# Leds_and_Buttons.net
KiCad netlist of a schematic drawn in Altium Designer
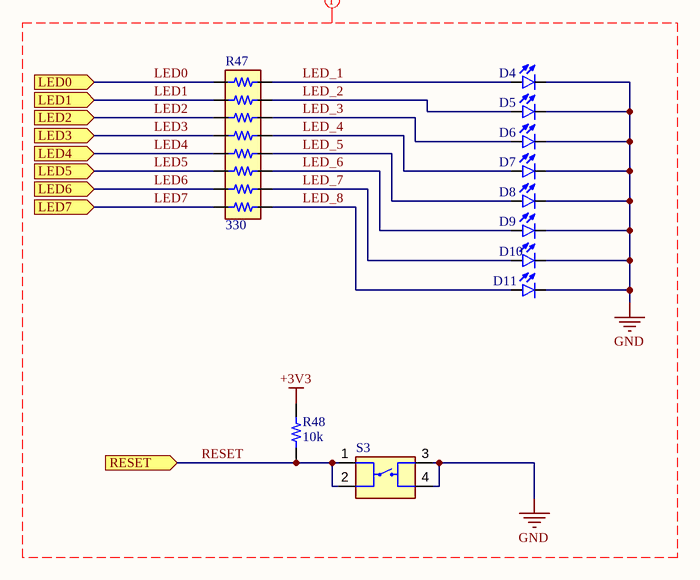
[diagram p0: Leds_and_Buttons.SchDoc]

(export (version "E")
  (design (tool "Eeschema 10.0.6"))
  (components
    (comp (ref "D4")
      (value "597-3305-607F")
      (footprint "0603_LED")
      (description "LED blue diffused 0603 SMD")
      (libsource (lib "Integrated_Circuits") (part "LED_BLUE_0603"))
    )
    (comp (ref "D5")
      (value "597-3305-607F")
      (footprint "0603_LED")
      (description "LED blue diffused 0603 SMD")
      (libsource (lib "Integrated_Circuits") (part "LED_BLUE_0603"))
    )
    (comp (ref "D6")
      (value "597-3305-607F")
      (footprint "0603_LED")
      (description "LED blue diffused 0603 SMD")
      (libsource (lib "Integrated_Circuits") (part "LED_BLUE_0603"))
    )
    (comp (ref "D7")
      (value "597-3305-607F")
      (footprint "0603_LED")
      (description "LED blue diffused 0603 SMD")
      (libsource (lib "Integrated_Circuits") (part "LED_BLUE_0603"))
    )
    (comp (ref "D8")
      (value "597-3305-607F")
      (footprint "0603_LED")
      (description "LED blue diffused 0603 SMD")
      (libsource (lib "Integrated_Circuits") (part "LED_BLUE_0603"))
    )
    (comp (ref "D9")
      (value "597-3305-607F")
      (footprint "0603_LED")
      (description "LED blue diffused 0603 SMD")
      (libsource (lib "Integrated_Circuits") (part "LED_BLUE_0603"))
    )
    (comp (ref "D10")
      (value "597-3305-607F")
      (footprint "0603_LED")
      (description "LED blue diffused 0603 SMD")
      (libsource (lib "Integrated_Circuits") (part "LED_BLUE_0603"))
    )
    (comp (ref "D11")
      (value "597-3305-607F")
      (footprint "0603_LED")
      (description "LED blue diffused 0603 SMD")
      (libsource (lib "Integrated_Circuits") (part "LED_BLUE_0603"))
    )
    (comp (ref "R47")
      (value "330")
      (footprint "ArrayResistor-1506")
      (description "RES ARRAY 8 RES 330 OHM 1506")
      (libsource (lib "Pasivos") (part "EXB-2HV331JV"))
    )
    (comp (ref "R48")
      (value "10k")
      (footprint "RES0402")
      (description "RES SMD 10K OHM 1% 0.063W 0402")
      (fields (field (name "TOLERANCE") "1%") (field (name "PARTNUMBER") "CRCW040210K0FK"))
      (libsource (lib "Pasivos") (part "CRCW040210K0FK"))
    )
    (comp (ref "S3")
      (value "PTS526 SK15 SMTR2 LFS")
      (footprint "Push Button")
      (description "SWITCH TACTILE SPST-NO 0.05A 12V")
      (libsource (lib "Pasivos") (part "PTS526 SK15 SMTR2 LFS"))
    )
  )
  (nets
    (net (code "1") (name "+3V3") (class "Default")
      (node (ref "R48") (pin "2") (pinfunction "2_2") (pintype "passive"))
    )
    (net (code "2") (name "/LED0") (class "Default")
      (node (ref "R47") (pin "1") (pinfunction "1_1") (pintype "passive"))
    )
    (net (code "3") (name "/LED1") (class "Default")
      (node (ref "R47") (pin "2") (pinfunction "2_2") (pintype "passive"))
    )
    (net (code "4") (name "/LED2") (class "Default")
      (node (ref "R47") (pin "3") (pinfunction "3_3") (pintype "passive"))
    )
    (net (code "5") (name "/LED3") (class "Default")
      (node (ref "R47") (pin "4") (pinfunction "4_4") (pintype "passive"))
    )
    (net (code "6") (name "/LED4") (class "Default")
      (node (ref "R47") (pin "5") (pinfunction "5_5") (pintype "passive"))
    )
    (net (code "7") (name "/LED5") (class "Default")
      (node (ref "R47") (pin "6") (pinfunction "6_6") (pintype "passive"))
    )
    (net (code "8") (name "/LED6") (class "Default")
      (node (ref "R47") (pin "7") (pinfunction "7_7") (pintype "passive"))
    )
    (net (code "9") (name "/LED7") (class "Default")
      (node (ref "R47") (pin "8") (pinfunction "8_8") (pintype "passive"))
    )
    (net (code "10") (name "/LED_1") (class "Default")
      (node (ref "D4") (pin "A") (pinfunction "A_A") (pintype "passive"))
      (node (ref "R47") (pin "16") (pinfunction "16_16") (pintype "passive"))
    )
    (net (code "11") (name "/LED_2") (class "Default")
      (node (ref "D5") (pin "A") (pinfunction "A_A") (pintype "passive"))
      (node (ref "R47") (pin "15") (pinfunction "15_15") (pintype "passive"))
    )
    (net (code "12") (name "/LED_3") (class "Default")
      (node (ref "D6") (pin "A") (pinfunction "A_A") (pintype "passive"))
      (node (ref "R47") (pin "14") (pinfunction "14_14") (pintype "passive"))
    )
    (net (code "13") (name "/LED_4") (class "Default")
      (node (ref "D7") (pin "A") (pinfunction "A_A") (pintype "passive"))
      (node (ref "R47") (pin "13") (pinfunction "13_13") (pintype "passive"))
    )
    (net (code "14") (name "/LED_5") (class "Default")
      (node (ref "D8") (pin "A") (pinfunction "A_A") (pintype "passive"))
      (node (ref "R47") (pin "12") (pinfunction "12_12") (pintype "passive"))
    )
    (net (code "15") (name "/LED_6") (class "Default")
      (node (ref "D9") (pin "A") (pinfunction "A_A") (pintype "passive"))
      (node (ref "R47") (pin "11") (pinfunction "11_11") (pintype "passive"))
    )
    (net (code "16") (name "/LED_7") (class "Default")
      (node (ref "D10") (pin "A") (pinfunction "A_A") (pintype "passive"))
      (node (ref "R47") (pin "10") (pinfunction "10_10") (pintype "passive"))
    )
    (net (code "17") (name "/LED_8") (class "Default")
      (node (ref "D11") (pin "A") (pinfunction "A_A") (pintype "passive"))
      (node (ref "R47") (pin "9") (pinfunction "9_9") (pintype "passive"))
    )
    (net (code "18") (name "/RESET") (class "Default")
      (node (ref "R48") (pin "1") (pinfunction "1_1") (pintype "passive"))
      (node (ref "S3") (pin "1") (pinfunction "1_1") (pintype "passive"))
      (node (ref "S3") (pin "2") (pinfunction "2_2") (pintype "passive"))
    )
    (net (code "19") (name "GND") (class "Default")
      (node (ref "D10") (pin "C") (pinfunction "C_C") (pintype "passive"))
      (node (ref "D11") (pin "C") (pinfunction "C_C") (pintype "passive"))
      (node (ref "D4") (pin "C") (pinfunction "C_C") (pintype "passive"))
      (node (ref "D5") (pin "C") (pinfunction "C_C") (pintype "passive"))
      (node (ref "D6") (pin "C") (pinfunction "C_C") (pintype "passive"))
      (node (ref "D7") (pin "C") (pinfunction "C_C") (pintype "passive"))
      (node (ref "D8") (pin "C") (pinfunction "C_C") (pintype "passive"))
      (node (ref "D9") (pin "C") (pinfunction "C_C") (pintype "passive"))
      (node (ref "S3") (pin "3") (pinfunction "3_3") (pintype "passive"))
      (node (ref "S3") (pin "4") (pinfunction "4_4") (pintype "passive"))
    )
  )
)
